# BACKPMAN21_Charger.net
KiCad netlist of a schematic drawn in Altium Designer
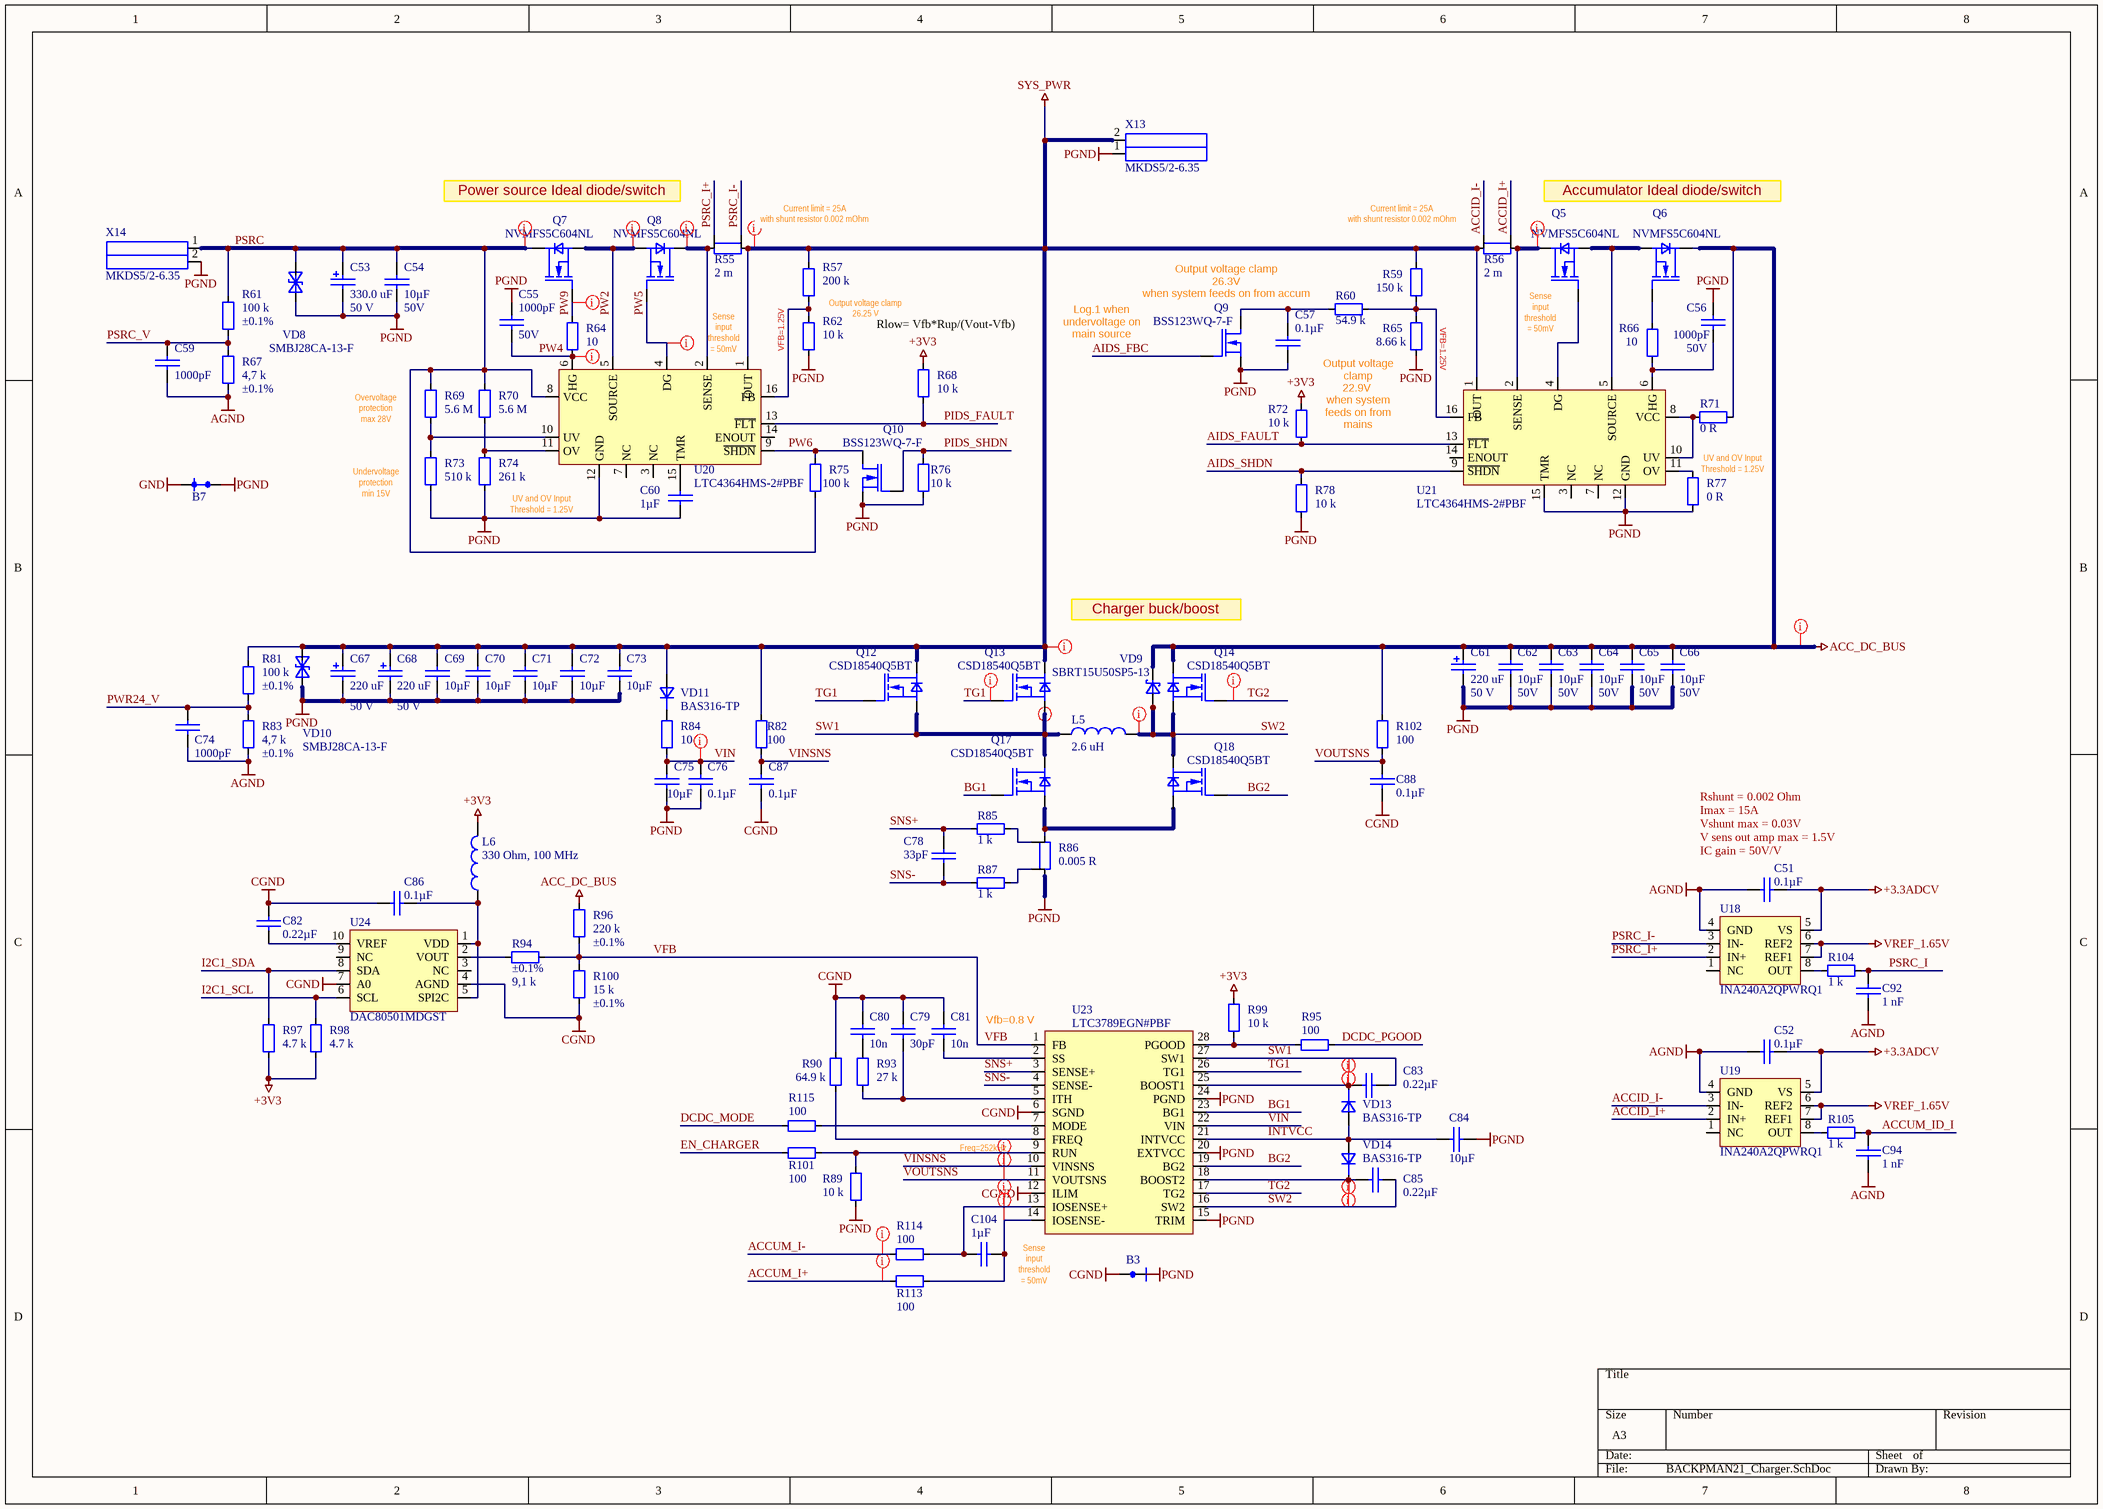
[diagram p0: BACKPMAN21_Charger.SchDoc]

(export (version "E")
  (design (tool "Eeschema 10.0.6"))
  (components
    (comp (ref "B3")
      (value "Net tie 0.3mm")
      (footprint "Net tee 0.3 mm")
      (libsource (lib "ea_Mechanical") (part "Net tie 0.3mm"))
    )
    (comp (ref "B7")
      (value "Net tie 1206")
      (footprint "Net tee 1206")
      (libsource (lib "ea_Mechanical") (part "Net tie 1206"))
    )
    (comp (ref "C51")
      (value "0.1µF")
      (footprint "0603 CAP")
      (description "0.1µF, ±10%, 50V, X8L, 0603 (1608 Metric), -55°C ~ 150°C, -, Automotive")
      (fields
        (field (name "PART NUMBER") "GCM188L81H104KA57D")
        (field (name "MANUFACTURER") "Murata Electronics North America")
      )
      (libsource (lib "ea_PassivComps") (part "Capacitor"))
    )
    (comp (ref "C52")
      (value "0.1µF")
      (footprint "0603 CAP")
      (description "0.1µF, ±10%, 50V, X8L, 0603 (1608 Metric), -55°C ~ 150°C, -, Automotive")
      (fields
        (field (name "PART NUMBER") "GCM188L81H104KA57D")
        (field (name "MANUFACTURER") "Murata Electronics North America")
      )
      (libsource (lib "ea_PassivComps") (part "Capacitor"))
    )
    (comp (ref "C53")
      (value "330.0 uF")
      (footprint "UUD1V331MNL1GS")
      (description "330 uF, 50V, 120 mOhm @ 100kHz, 585 mA, 10x10, -50...+105 C")
      (fields
        (field (name "MANUFACTURER") "Panasonic Electronic Components")
        (field (name "VOLTAGE") "50 V")
        (field (name "TOLERANCE") "±20%")
      )
      (libsource (lib "ea_Capacitors") (part "EEE-FT1H331GP"))
    )
    (comp (ref "C54")
      (value "10µF")
      (footprint "1210 CAP")
      (description "10µF, ±10%, 50V, X7S, 1210 (3225 Metric), -55°C ~ 125°C, Low ESL, General Purpose")
      (fields
        (field (name "VOLTAGE - RATED") "50V")
        (field (name "PART NUMBER") "C3225X7S1H106K250AB")
        (field (name "MANUFACTURER") "TDK Corporation")
      )
      (libsource (lib "ea_PassivComps") (part "Capacitor"))
    )
    (comp (ref "C55")
      (value "1000pF")
      (footprint "0603 CAP")
      (description "1000pF, ±10%, 50V, X7R, 0603 (1608 Metric), -55°C ~ 125°C, -, General Purpose")
      (fields
        (field (name "VOLTAGE - RATED") "50V")
        (field (name "PART NUMBER") "CL10B102KB8NNWC")
        (field (name "MANUFACTURER") "Samsung Electro-Mechanics")
      )
      (libsource (lib "ea_PassivComps") (part "Capacitor"))
    )
    (comp (ref "C56")
      (value "1000pF")
      (footprint "0603 CAP")
      (description "1000pF, ±10%, 50V, X7R, 0603 (1608 Metric), -55°C ~ 125°C, -, General Purpose")
      (fields
        (field (name "VOLTAGE - RATED") "50V")
        (field (name "PART NUMBER") "CL10B102KB8NNWC")
        (field (name "MANUFACTURER") "Samsung Electro-Mechanics")
      )
      (libsource (lib "ea_PassivComps") (part "Capacitor"))
    )
    (comp (ref "C57")
      (value "0.1µF")
      (footprint "0603 CAP")
      (description "0.1µF, ±10%, 16V, X7R, 0603 (1608 Metric), -55°C ~ 125°C, -, General Purpose")
      (fields
        (field (name "PART NUMBER") "CL10B104KO8NNNC")
        (field (name "MANUFACTURER") "Samsung Electro-Mechanics")
      )
      (libsource (lib "ea_PassivComps") (part "Capacitor"))
    )
    (comp (ref "C59")
      (value "1000pF")
      (footprint "0603 CAP")
      (description "1000pF, ±10%, 16V, X7R, 0603 (1608 Metric), -55°C ~ 125°C, -, General Purpose")
      (fields
        (field (name "PART NUMBER") "885012206034")
        (field (name "MANUFACTURER") "Wurth Electronics Inc.")
      )
      (libsource (lib "ea_PassivComps") (part "Capacitor"))
    )
    (comp (ref "C60")
      (value "1µF")
      (footprint "0603 CAP")
      (description "1µF, ±10%, 16V, X7R, 0603 (1608 Metric), -55°C ~ 125°C, -, General Purpose")
      (fields
        (field (name "PART NUMBER") "CL10B105KO8NNNC")
        (field (name "MANUFACTURER") "Samsung Electro-Mechanics")
      )
      (libsource (lib "ea_PassivComps") (part "Capacitor"))
    )
    (comp (ref "C61")
      (value "220 uF")
      (footprint "Panasonic G")
      (description "220 uF, 50V, 13 mOhm, 3.7 A 100kHz, 16.8 mm height, 10.3x10.3 mm, -55...+105 C")
      (fields
        (field (name "MANUFACTURER") "Panasonic Electronic Components")
        (field (name "TOLERANCE") "±20%")
        (field (name "VOLTAGE") "50 V")
      )
      (libsource (lib "ea_Capacitors") (part "EEH-ZS1H221P"))
    )
    (comp (ref "C62")
      (value "10µF")
      (footprint "1210 CAP")
      (description "10µF, ±10%, 50V, X7S, 1210 (3225 Metric), -55°C ~ 125°C, Low ESL, General Purpose")
      (fields
        (field (name "VOLTAGE - RATED") "50V")
        (field (name "PART NUMBER") "C3225X7S1H106K250AB")
        (field (name "MANUFACTURER") "TDK Corporation")
      )
      (libsource (lib "ea_PassivComps") (part "Capacitor"))
    )
    (comp (ref "C63")
      (value "10µF")
      (footprint "1210 CAP")
      (description "10µF, ±10%, 50V, X7S, 1210 (3225 Metric), -55°C ~ 125°C, Low ESL, General Purpose")
      (fields
        (field (name "VOLTAGE - RATED") "50V")
        (field (name "PART NUMBER") "C3225X7S1H106K250AB")
        (field (name "MANUFACTURER") "TDK Corporation")
      )
      (libsource (lib "ea_PassivComps") (part "Capacitor"))
    )
    (comp (ref "C64")
      (value "10µF")
      (footprint "1210 CAP")
      (description "10µF, ±10%, 50V, X7S, 1210 (3225 Metric), -55°C ~ 125°C, Low ESL, General Purpose")
      (fields
        (field (name "VOLTAGE - RATED") "50V")
        (field (name "PART NUMBER") "C3225X7S1H106K250AB")
        (field (name "MANUFACTURER") "TDK Corporation")
      )
      (libsource (lib "ea_PassivComps") (part "Capacitor"))
    )
    (comp (ref "C65")
      (value "10µF")
      (footprint "1210 CAP")
      (description "10µF, ±10%, 50V, X7S, 1210 (3225 Metric), -55°C ~ 125°C, Low ESL, General Purpose")
      (fields
        (field (name "VOLTAGE - RATED") "50V")
        (field (name "PART NUMBER") "C3225X7S1H106K250AB")
        (field (name "MANUFACTURER") "TDK Corporation")
      )
      (libsource (lib "ea_PassivComps") (part "Capacitor"))
    )
    (comp (ref "C66")
      (value "10µF")
      (footprint "1210 CAP")
      (description "10µF, ±10%, 50V, X7S, 1210 (3225 Metric), -55°C ~ 125°C, Low ESL, General Purpose")
      (fields
        (field (name "VOLTAGE - RATED") "50V")
        (field (name "PART NUMBER") "C3225X7S1H106K250AB")
        (field (name "MANUFACTURER") "TDK Corporation")
      )
      (libsource (lib "ea_PassivComps") (part "Capacitor"))
    )
    (comp (ref "C67")
      (value "220 uF")
      (footprint "Panasonic G")
      (description "220 uF, 50V, 13 mOhm, 3.7 A 100kHz, 16.8 mm height, 10.3x10.3 mm, -55...+105 C")
      (fields
        (field (name "MANUFACTURER") "Panasonic Electronic Components")
        (field (name "TOLERANCE") "±20%")
        (field (name "VOLTAGE") "50 V")
      )
      (libsource (lib "ea_Capacitors") (part "EEH-ZS1H221P"))
    )
    (comp (ref "C68")
      (value "220 uF")
      (footprint "Panasonic G")
      (description "220 uF, 50V, 13 mOhm, 3.7 A 100kHz, 16.8 mm height, 10.3x10.3 mm, -55...+105 C")
      (fields
        (field (name "MANUFACTURER") "Panasonic Electronic Components")
        (field (name "TOLERANCE") "±20%")
        (field (name "VOLTAGE") "50 V")
      )
      (libsource (lib "ea_Capacitors") (part "EEH-ZS1H221P"))
    )
    (comp (ref "C69")
      (value "10µF")
      (footprint "1210 CAP")
      (description "10µF, ±10%, 50V, X7S, 1210 (3225 Metric), -55°C ~ 125°C, Low ESL, General Purpose")
      (fields
        (field (name "PART NUMBER") "C3225X7S1H106K250AB")
        (field (name "MANUFACTURER") "TDK Corporation")
      )
      (libsource (lib "ea_PassivComps") (part "Capacitor"))
    )
    (comp (ref "C70")
      (value "10µF")
      (footprint "1210 CAP")
      (description "10µF, ±10%, 50V, X7S, 1210 (3225 Metric), -55°C ~ 125°C, Low ESL, General Purpose")
      (fields
        (field (name "PART NUMBER") "C3225X7S1H106K250AB")
        (field (name "MANUFACTURER") "TDK Corporation")
      )
      (libsource (lib "ea_PassivComps") (part "Capacitor"))
    )
    (comp (ref "C71")
      (value "10µF")
      (footprint "1210 CAP")
      (description "10µF, ±10%, 50V, X7S, 1210 (3225 Metric), -55°C ~ 125°C, Low ESL, General Purpose")
      (fields
        (field (name "PART NUMBER") "C3225X7S1H106K250AB")
        (field (name "MANUFACTURER") "TDK Corporation")
      )
      (libsource (lib "ea_PassivComps") (part "Capacitor"))
    )
    (comp (ref "C72")
      (value "10µF")
      (footprint "1210 CAP")
      (description "10µF, ±10%, 50V, X7S, 1210 (3225 Metric), -55°C ~ 125°C, Low ESL, General Purpose")
      (fields
        (field (name "PART NUMBER") "C3225X7S1H106K250AB")
        (field (name "MANUFACTURER") "TDK Corporation")
      )
      (libsource (lib "ea_PassivComps") (part "Capacitor"))
    )
    (comp (ref "C73")
      (value "10µF")
      (footprint "1210 CAP")
      (description "10µF, ±10%, 50V, X7S, 1210 (3225 Metric), -55°C ~ 125°C, Low ESL, General Purpose")
      (fields
        (field (name "PART NUMBER") "C3225X7S1H106K250AB")
        (field (name "MANUFACTURER") "TDK Corporation")
      )
      (libsource (lib "ea_PassivComps") (part "Capacitor"))
    )
    (comp (ref "C74")
      (value "1000pF")
      (footprint "0603 CAP")
      (description "1000pF, ±10%, 16V, X7R, 0603 (1608 Metric), -55°C ~ 125°C, -, General Purpose")
      (fields
        (field (name "PART NUMBER") "885012206034")
        (field (name "MANUFACTURER") "Wurth Electronics Inc.")
      )
      (libsource (lib "ea_PassivComps") (part "Capacitor"))
    )
    (comp (ref "C75")
      (value "10µF")
      (footprint "1210 CAP")
      (description "10µF, ±10%, 50V, X7S, 1210 (3225 Metric), -55°C ~ 125°C, Low ESL, General Purpose")
      (fields
        (field (name "PART NUMBER") "C3225X7S1H106K250AB")
        (field (name "MANUFACTURER") "TDK Corporation")
      )
      (libsource (lib "ea_PassivComps") (part "Capacitor"))
    )
    (comp (ref "C76")
      (value "0.1µF")
      (footprint "0603 CAP")
      (description "0.1µF, ±10%, 50V, X8L, 0603 (1608 Metric), -55°C ~ 150°C, -, Automotive")
      (fields
        (field (name "PART NUMBER") "GCM188L81H104KA57D")
        (field (name "MANUFACTURER") "Murata Electronics North America")
      )
      (libsource (lib "ea_PassivComps") (part "Capacitor"))
    )
    (comp (ref "C78")
      (value "33pF")
      (footprint "0603 CAP")
      (description "33pF, ±5%, 50V, C0G, NP0, 0603 (1608 Metric), -55°C ~ 125°C, -, General Purpose")
      (fields
        (field (name "PART NUMBER") "885012006054")
        (field (name "MANUFACTURER") "Wurth Electronics Inc.")
      )
      (libsource (lib "ea_PassivComps") (part "Capacitor"))
    )
    (comp (ref "C79")
      (value "30pF")
      (footprint "0603 CAP")
      (description "30pF, ±5%, 50V, C0G, NP0, 0603 (1608 Metric), -55°C ~ 125°C, -, General Purpose")
      (fields
        (field (name "PART NUMBER") "CL10C300JB8NCNC")
        (field (name "MANUFACTURER") "Samsung Electro-Mechanics")
      )
      (libsource (lib "ea_PassivComps") (part "Capacitor"))
    )
    (comp (ref "C80")
      (value "10n")
      (footprint "0603 CAP")
      (description "10000pF, ±10%, 25V, X7R, 0603 (1608 Metric), -55°C ~ 125°C, -, General Purpose")
      (fields (field (name "PART NUMBER") "C0603C103K3RACTU") (field (name "MANUFACTURER") "KEMET"))
      (libsource (lib "ea_PassivComps") (part "Capacitor"))
    )
    (comp (ref "C81")
      (value "10n")
      (footprint "0603 CAP")
      (description "10000pF, ±10%, 25V, X7R, 0603 (1608 Metric), -55°C ~ 125°C, -, General Purpose")
      (fields (field (name "PART NUMBER") "C0603C103K3RACTU") (field (name "MANUFACTURER") "KEMET"))
      (libsource (lib "ea_PassivComps") (part "Capacitor"))
    )
    (comp (ref "C82")
      (value "0.22µF")
      (footprint "0603 CAP")
      (description "0.22µF, ±10%, 16V, X7R, 0603 (1608 Metric), -55°C ~ 125°C, -, General Purpose")
      (fields
        (field (name "PART NUMBER") "GRM188R71C224KA01J")
        (field (name "MANUFACTURER") "Murata Electronics North America")
      )
      (libsource (lib "ea_PassivComps") (part "Capacitor"))
    )
    (comp (ref "C83")
      (value "0.22µF")
      (footprint "0603 CAP")
      (description "0.22µF, ±10%, 16V, X7R, 0603 (1608 Metric), -55°C ~ 125°C, -, General Purpose")
      (fields
        (field (name "PART NUMBER") "GRM188R71C224KA01J")
        (field (name "MANUFACTURER") "Murata Electronics North America")
      )
      (libsource (lib "ea_PassivComps") (part "Capacitor"))
    )
    (comp (ref "C84")
      (value "10µF")
      (footprint "0603 CAP")
      (description "10µF, ±20%, 25V, X5R, 0603 (1608 Metric), -55°C ~ 85°C, Low ESL, General Purpose")
      (fields
        (field (name "PART NUMBER") "C1608X5R1E106M080AC")
        (field (name "MANUFACTURER") "TDK Corporation")
      )
      (libsource (lib "ea_PassivComps") (part "Capacitor"))
    )
    (comp (ref "C85")
      (value "0.22µF")
      (footprint "0603 CAP")
      (description "0.22µF, ±10%, 16V, X7R, 0603 (1608 Metric), -55°C ~ 125°C, -, General Purpose")
      (fields
        (field (name "PART NUMBER") "GRM188R71C224KA01J")
        (field (name "MANUFACTURER") "Murata Electronics North America")
      )
      (libsource (lib "ea_PassivComps") (part "Capacitor"))
    )
    (comp (ref "C86")
      (value "0.1µF")
      (footprint "0603 CAP")
      (description "0.1µF, ±10%, 16V, X7R, 0603 (1608 Metric), -55°C ~ 125°C, -, General Purpose")
      (fields
        (field (name "PART NUMBER") "CL10B104KO8NNNC")
        (field (name "MANUFACTURER") "Samsung Electro-Mechanics")
      )
      (libsource (lib "ea_PassivComps") (part "Capacitor"))
    )
    (comp (ref "C87")
      (value "0.1µF")
      (footprint "0603 CAP")
      (description "0.1µF, ±10%, 50V, X8L, 0603 (1608 Metric), -55°C ~ 150°C, -, Automotive")
      (fields
        (field (name "PART NUMBER") "GCM188L81H104KA57D")
        (field (name "MANUFACTURER") "Murata Electronics North America")
      )
      (libsource (lib "ea_PassivComps") (part "Capacitor"))
    )
    (comp (ref "C88")
      (value "0.1µF")
      (footprint "0603 CAP")
      (description "0.1µF, ±10%, 50V, X8L, 0603 (1608 Metric), -55°C ~ 150°C, -, Automotive")
      (fields
        (field (name "PART NUMBER") "GCM188L81H104KA57D")
        (field (name "MANUFACTURER") "Murata Electronics North America")
      )
      (libsource (lib "ea_PassivComps") (part "Capacitor"))
    )
    (comp (ref "C92")
      (value "1 nF")
      (footprint "0603 CAP")
      (description "1000pF, ±5%, 50V, X7R, 0603 (1608 Metric), -55°C ~ 125°C, -, General Purpose")
      (fields (field (name "PART NUMBER") "CC0603JRX7R9BB102") (field (name "MANUFACTURER") "Yageo"))
      (libsource (lib "ea_PassivComps") (part "Capacitor"))
    )
    (comp (ref "C94")
      (value "1 nF")
      (footprint "0603 CAP")
      (description "1000pF, ±5%, 50V, X7R, 0603 (1608 Metric), -55°C ~ 125°C, -, General Purpose")
      (fields (field (name "PART NUMBER") "CC0603JRX7R9BB102") (field (name "MANUFACTURER") "Yageo"))
      (libsource (lib "ea_PassivComps") (part "Capacitor"))
    )
    (comp (ref "C104")
      (value "1µF")
      (footprint "0603 CAP")
      (description "1µF, ±10%, 16V, X7R, 0603 (1608 Metric), -55°C ~ 125°C, -, General Purpose")
      (fields
        (field (name "PART NUMBER") "CL10B105KO8NNNC")
        (field (name "MANUFACTURER") "Samsung Electro-Mechanics")
      )
      (libsource (lib "ea_PassivComps") (part "Capacitor"))
    )
    (comp (ref "L5")
      (value "2.6 uH")
      (footprint "7443556260   Wurth Elektronik")
      (description "2.6 uH, 31.5 A, ±20%, 1.58 mOhm, -40°C ~ 125°C")
      (fields (field (name "MANUFACTURER") "Würth Elektronik") (field (name "PARTNUM") "732-2170-1-ND"))
      (libsource (lib "ea_Inductors") (part "7443556260"))
    )
    (comp (ref "L6")
      (value "330 Ohm, 100 MHz")
      (footprint "0603")
      (description "Ferrite bead, 330 Ohm, 100 MHz,  1.5 A, 0.07 Ohm")
      (fields
        (field (name "MANUFACTURER") "Murata Electronics North America")
        (field (name "PARTNUM") "BLM18SG331TN1D")
      )
      (libsource (lib "*") (part "BLM18SG331TN1D"))
    )
    (comp (ref "Q5")
      (value "NVMFS5C604NL")
      (footprint "SO8FL Universal Footprint")
      (description "MOSFET N-CH, 287 A, 60V, Vgs=±20V, 1.2 mOhm, 52nC @ 4.5V, 5-DFN (5x6), -55°C ~ 175°C")
      (fields
        (field (name "MANUFACTURER") "Texas Instruments")
        (field (name "PARTNUM") "NVMFS5C604NLAFT1GOSCT-ND")
      )
      (libsource (lib "ea_MOSFET_&_drivers") (part "NVMFS5C604NLAFT1G"))
    )
    (comp (ref "Q6")
      (value "NVMFS5C604NL")
      (footprint "SO8FL Universal Footprint")
      (description "MOSFET N-CH, 287 A, 60V, Vgs=±20V, 1.2 mOhm, 52nC @ 4.5V, 5-DFN (5x6), -55°C ~ 175°C")
      (fields
        (field (name "MANUFACTURER") "Texas Instruments")
        (field (name "PARTNUM") "NVMFS5C604NLAFT1GOSCT-ND")
      )
      (libsource (lib "ea_MOSFET_&_drivers") (part "NVMFS5C604NLAFT1G"))
    )
    (comp (ref "Q7")
      (value "NVMFS5C604NL")
      (footprint "SO8FL Universal Footprint")
      (description "MOSFET N-CH, 287 A, 60V, Vgs=±20V, 1.2 mOhm, 52nC @ 4.5V, 5-DFN (5x6), -55°C ~ 175°C")
      (fields
        (field (name "MANUFACTURER") "Texas Instruments")
        (field (name "PARTNUM") "NVMFS5C604NLAFT1GOSCT-ND")
      )
      (libsource (lib "ea_MOSFET_&_drivers") (part "NVMFS5C604NLAFT1G"))
    )
    (comp (ref "Q8")
      (value "NVMFS5C604NL")
      (footprint "SO8FL Universal Footprint")
      (description "MOSFET N-CH, 287 A, 60V, Vgs=±20V, 1.2 mOhm, 52nC @ 4.5V, 5-DFN (5x6), -55°C ~ 175°C")
      (fields
        (field (name "MANUFACTURER") "Texas Instruments")
        (field (name "PARTNUM") "NVMFS5C604NLAFT1GOSCT-ND")
      )
      (libsource (lib "ea_MOSFET_&_drivers") (part "NVMFS5C604NLAFT1G"))
    )
    (comp (ref "Q9")
      (value "BSS123WQ-7-F")
      (footprint "SOT323-3")
      (description "MOSFETs N-CH, 2V @ 1mA, 6 Ohm @ 170mA, 10V, 170mA, 100V, SOT-323,  -55°C ~ 150°C")
      (fields
        (field (name "MANUFACTURER") "Diodes Incorporated")
        (field (name "PARTNUM") "BSS123WQ-7-FDICT-ND")
      )
      (libsource (lib "") (part "BSS123WQ-7-F_1"))
    )
    (comp (ref "Q10")
      (value "BSS123WQ-7-F")
      (footprint "SOT323-3")
      (description "MOSFETs N-CH, 2V @ 1mA, 6 Ohm @ 170mA, 10V, 170mA, 100V, SOT-323,  -55°C ~ 150°C")
      (fields
        (field (name "MANUFACTURER") "Diodes Incorporated")
        (field (name "PARTNUM") "BSS123WQ-7-FDICT-ND")
      )
      (libsource (lib "ea_Transistors") (part "BSS123WQ-7-F"))
    )
    (comp (ref "Q12")
      (value "CSD18540Q5BT")
      (footprint "SO8FL Universal Footprint")
      (description "MOSFET N-CH, 100 A, 60V, Vgs=±20V, 1.8 mOhm, 41nC @ 10V, 5-DFN (5x6), -55°C ~ 150°C")
      (fields (field (name "MANUFACTURER") "Texas Instruments") (field (name "PARTNUM") "296-37963-1-ND"))
      (libsource (lib "") (part "CSD18540Q5BT_1"))
    )
    (comp (ref "Q13")
      (value "CSD18540Q5BT")
      (footprint "SO8FL Universal Footprint")
      (description "MOSFET N-CH, 100 A, 60V, Vgs=±20V, 1.8 mOhm, 41nC @ 10V, 5-DFN (5x6), -55°C ~ 150°C")
      (fields (field (name "MANUFACTURER") "Texas Instruments") (field (name "PARTNUM") "296-37963-1-ND"))
      (libsource (lib "") (part "CSD18540Q5BT_1"))
    )
    (comp (ref "Q14")
      (value "CSD18540Q5BT")
      (footprint "SO8FL Universal Footprint")
      (description "MOSFET N-CH, 100 A, 60V, Vgs=±20V, 1.8 mOhm, 41nC @ 10V, 5-DFN (5x6), -55°C ~ 150°C")
      (fields (field (name "MANUFACTURER") "Texas Instruments") (field (name "PARTNUM") "296-37963-1-ND"))
      (libsource (lib "ea_MOSFET_&_drivers") (part "CSD18540Q5BT"))
    )
    (comp (ref "Q17")
      (value "CSD18540Q5BT")
      (footprint "SO8FL Universal Footprint")
      (description "MOSFET N-CH, 100 A, 60V, Vgs=±20V, 1.8 mOhm, 41nC @ 10V, 5-DFN (5x6), -55°C ~ 150°C")
      (fields (field (name "MANUFACTURER") "Texas Instruments") (field (name "PARTNUM") "296-37963-1-ND"))
      (libsource (lib "") (part "CSD18540Q5BT_1"))
    )
    (comp (ref "Q18")
      (value "CSD18540Q5BT")
      (footprint "SO8FL Universal Footprint")
      (description "MOSFET N-CH, 100 A, 60V, Vgs=±20V, 1.8 mOhm, 41nC @ 10V, 5-DFN (5x6), -55°C ~ 150°C")
      (fields (field (name "MANUFACTURER") "Texas Instruments") (field (name "PARTNUM") "296-37963-1-ND"))
      (libsource (lib "ea_MOSFET_&_drivers") (part "CSD18540Q5BT"))
    )
    (comp (ref "R55")
      (value "2 m")
      (footprint "2512 shunt")
      (fields
        (field (name "MANUFACTURER") "Vishay Dale")
        (field (name "TOLERANCE") "±1%")
        (field (name "PARTNUM") "541-3126-1-ND")
      )
      (libsource (lib "ea_PassivComps") (part "Resistor_shunt"))
    )
    (comp (ref "R56")
      (value "2 m")
      (footprint "2512 shunt")
      (fields
        (field (name "MANUFACTURER") "Vishay Dale")
        (field (name "TOLERANCE") "±1%")
        (field (name "PARTNUM") "541-3126-1-ND")
      )
      (libsource (lib "ea_PassivComps") (part "Resistor_shunt"))
    )
    (comp (ref "R57")
      (value "200 k")
      (footprint "1206")
      (fields
        (field (name "MANUFACTURER") "Stackpole Electronics Inc.")
        (field (name "TOLERANCE") "±1%")
        (field (name "VOLTAGE") "200V")
      )
      (libsource (lib "ea_PassivComps") (part "Resistor"))
    )
    (comp (ref "R59")
      (value "150 k")
      (footprint "1206")
      (fields
        (field (name "MANUFACTURER") "Stackpole Electronics Inc.")
        (field (name "TOLERANCE") "±1%")
        (field (name "VOLTAGE") "200V")
      )
      (libsource (lib "") (part "Resistor_3"))
    )
    (comp (ref "R60")
      (value "54.9 k")
      (footprint "0603")
      (fields
        (field (name "MANUFACTURER") "Stackpole Electronics Inc.")
        (field (name "TOLERANCE") "±1%")
        (field (name "VOLTAGE") "75V")
      )
      (libsource (lib "") (part "Resistor_1"))
    )
    (comp (ref "R61")
      (value "100 k")
      (footprint "1206")
      (fields
        (field (name "MANUFACTURER") "Panasonic Electronic Components")
        (field (name "TOLERANCE") "±0.1%")
        (field (name "VOLTAGE") "200V")
        (field (name "PARTNUM") "ERA-8APB104V")
      )
      (libsource (lib "") (part "Resistor_3"))
    )
    (comp (ref "R62")
      (value "10 k")
      (footprint "0603")
      (fields
        (field (name "MANUFACTURER") "Bourns Inc.")
        (field (name "TOLERANCE") "±1%")
        (field (name "VOLTAGE") "75V")
      )
      (libsource (lib "") (part "Resistor_1"))
    )
    (comp (ref "R64")
      (value "10")
      (footprint "0805")
      (fields
        (field (name "MANUFACTURER") "Stackpole Electronics Inc.")
        (field (name "TOLERANCE") "±1%")
        (field (name "VOLTAGE") "150V")
      )
      (libsource (lib "ea_PassivComps") (part "Resistor"))
    )
    (comp (ref "R65")
      (value "8.66 k")
      (footprint "0603")
      (fields
        (field (name "MANUFACTURER") "Stackpole Electronics Inc.")
        (field (name "TOLERANCE") "±1%")
        (field (name "VOLTAGE") "75V")
      )
      (libsource (lib "") (part "Resistor_3"))
    )
    (comp (ref "R66")
      (value "10")
      (footprint "0805")
      (fields
        (field (name "MANUFACTURER") "Stackpole Electronics Inc.")
        (field (name "TOLERANCE") "±1%")
        (field (name "VOLTAGE") "150V")
      )
      (libsource (lib "") (part "Resistor_3"))
    )
    (comp (ref "R67")
      (value "4,7 k")
      (footprint "0603")
      (fields
        (field (name "MANUFACTURER") "Panasonic Electronic Components")
        (field (name "TOLERANCE") "±0.1%")
        (field (name "VOLTAGE") "75V")
        (field (name "PARTNUM") "P4.7KDBCT-ND")
      )
      (libsource (lib "ea_PassivComps") (part "Resistor"))
    )
    (comp (ref "R68")
      (value "10 k")
      (footprint "0603")
      (fields
        (field (name "MANUFACTURER") "Bourns Inc.")
        (field (name "TOLERANCE") "±1%")
        (field (name "VOLTAGE") "75V")
      )
      (libsource (lib "ea_PassivComps") (part "Resistor"))
    )
    (comp (ref "R69")
      (value "5.6 M")
      (footprint "1206")
      (fields
        (field (name "MANUFACTURER") "Yageo")
        (field (name "TOLERANCE") "±1%")
        (field (name "VOLTAGE") "200V")
      )
      (libsource (lib "ea_PassivComps") (part "Resistor"))
    )
    (comp (ref "R70")
      (value "5.6 M")
      (footprint "1206")
      (fields
        (field (name "MANUFACTURER") "Yageo")
        (field (name "TOLERANCE") "±1%")
        (field (name "VOLTAGE") "200V")
      )
      (libsource (lib "ea_PassivComps") (part "Resistor"))
    )
    (comp (ref "R71")
      (value "0 R")
      (footprint "0603")
      (description "0 R, Jumper, 0603, SMD Resistor, -55°C ~ 155°C")
      (fields (field (name "MANUFACTURER") "Yageo") (field (name "VOLTAGE") "75 V"))
      (libsource (lib "") (part "RC0603FR-070RL_1"))
    )
    (comp (ref "R72")
      (value "10 k")
      (footprint "0603")
      (fields
        (field (name "MANUFACTURER") "Bourns Inc.")
        (field (name "TOLERANCE") "±1%")
        (field (name "VOLTAGE") "75V")
      )
      (libsource (lib "ea_PassivComps") (part "Resistor"))
    )
    (comp (ref "R73")
      (value "510 k")
      (footprint "0603")
      (fields
        (field (name "MANUFACTURER") "Stackpole Electronics Inc.")
        (field (name "TOLERANCE") "±1%")
        (field (name "VOLTAGE") "75V")
      )
      (libsource (lib "ea_PassivComps") (part "Resistor"))
    )
    (comp (ref "R74")
      (value "261 k")
      (footprint "0603")
      (fields
        (field (name "MANUFACTURER") "Vishay Dale")
        (field (name "TOLERANCE") "±1%")
        (field (name "VOLTAGE") "75V")
      )
      (libsource (lib "ea_PassivComps") (part "Resistor"))
    )
    (comp (ref "R75")
      (value "100 k")
      (footprint "1206")
      (fields
        (field (name "MANUFACTURER") "Stackpole Electronics Inc.")
        (field (name "TOLERANCE") "±1%")
        (field (name "VOLTAGE") "200V")
      )
      (libsource (lib "ea_PassivComps") (part "Resistor"))
    )
    (comp (ref "R76")
      (value "10 k")
      (footprint "0603")
      (fields
        (field (name "MANUFACTURER") "Bourns Inc.")
        (field (name "TOLERANCE") "±1%")
        (field (name "VOLTAGE") "75V")
      )
      (libsource (lib "ea_PassivComps") (part "Resistor"))
    )
    (comp (ref "R77")
      (value "0 R")
      (footprint "0603")
      (description "0 R, Jumper, 0603, SMD Resistor, -55°C ~ 155°C")
      (fields (field (name "MANUFACTURER") "Yageo") (field (name "VOLTAGE") "75 V"))
      (libsource (lib "ea_Resistors_0603") (part "RC0603FR-070RL"))
    )
    (comp (ref "R78")
      (value "10 k")
      (footprint "0603")
      (fields
        (field (name "MANUFACTURER") "Bourns Inc.")
        (field (name "TOLERANCE") "±1%")
        (field (name "VOLTAGE") "75V")
      )
      (libsource (lib "") (part "Resistor_3"))
    )
    (comp (ref "R81")
      (value "100 k")
      (footprint "1206")
      (fields
        (field (name "MANUFACTURER") "Panasonic Electronic Components")
        (field (name "TOLERANCE") "±0.1%")
        (field (name "VOLTAGE") "200V")
        (field (name "PARTNUM") "ERA-8APB104V")
      )
      (libsource (lib "") (part "Resistor_3"))
    )
    (comp (ref "R82")
      (value "100")
      (footprint "0603")
      (fields
        (field (name "MANUFACTURER") "Stackpole Electronics Inc.")
        (field (name "TOLERANCE") "±1%")
        (field (name "VOLTAGE") "75V")
      )
      (libsource (lib "ea_PassivComps") (part "Resistor"))
    )
    (comp (ref "R83")
      (value "4,7 k")
      (footprint "0603")
      (fields
        (field (name "MANUFACTURER") "Panasonic Electronic Components")
        (field (name "TOLERANCE") "±0.1%")
        (field (name "VOLTAGE") "75V")
        (field (name "PARTNUM") "P4.7KDBCT-ND")
      )
      (libsource (lib "ea_PassivComps") (part "Resistor"))
    )
    (comp (ref "R84")
      (value "10")
      (footprint "0805")
      (fields
        (field (name "MANUFACTURER") "Stackpole Electronics Inc.")
        (field (name "TOLERANCE") "±1%")
        (field (name "VOLTAGE") "150V")
      )
      (libsource (lib "ea_PassivComps") (part "Resistor"))
    )
    (comp (ref "R85")
      (value "1 k")
      (footprint "0603")
      (fields
        (field (name "MANUFACTURER") "Stackpole Electronics Inc.")
        (field (name "TOLERANCE") "±1%")
        (field (name "VOLTAGE") "75V")
      )
      (libsource (lib "") (part "Resistor_2"))
    )
    (comp (ref "R86")
      (value "0.005 R")
      (footprint "FC4L110")
      (description "Curr.sens.res. 0.005 OHM 5W 1% , 4320 (50110 Metric)")
      (fields (field (name "MANUFACTURER") "Ohmite") (field (name "TOLERANCE") "1%"))
      (libsource (lib "ea_Resistors") (part "FC4L110R005FER"))
    )
    (comp (ref "R87")
      (value "1 k")
      (footprint "0603")
      (fields
        (field (name "MANUFACTURER") "Stackpole Electronics Inc.")
        (field (name "TOLERANCE") "±1%")
        (field (name "VOLTAGE") "75V")
      )
      (libsource (lib "") (part "Resistor_2"))
    )
    (comp (ref "R89")
      (value "10 k")
      (footprint "0603")
      (fields
        (field (name "MANUFACTURER") "Bourns Inc.")
        (field (name "TOLERANCE") "±1%")
        (field (name "VOLTAGE") "75V")
      )
      (libsource (lib "ea_PassivComps") (part "Resistor"))
    )
    (comp (ref "R90")
      (value "64.9 k")
      (footprint "0603")
      (fields
        (field (name "MANUFACTURER") "Stackpole Electronics Inc.")
        (field (name "TOLERANCE") "±1%")
        (field (name "VOLTAGE") "75V")
      )
      (libsource (lib "") (part "Resistor_1"))
    )
    (comp (ref "R93")
      (value "27 k")
      (footprint "0603")
      (fields
        (field (name "MANUFACTURER") "Stackpole Electronics Inc.")
        (field (name "TOLERANCE") "±1%")
        (field (name "VOLTAGE") "75V")
      )
      (libsource (lib "ea_PassivComps") (part "Resistor"))
    )
    (comp (ref "R94")
      (value "9,1 k")
      (footprint "0603")
      (fields
        (field (name "MANUFACTURER") "Panasonic Electronic Components")
        (field (name "TOLERANCE") "±0.1%")
        (field (name "VOLTAGE") "75V")
        (field (name "PARTNUM") "P9.1KDBCT-ND")
      )
      (libsource (lib "") (part "Resistor_2"))
    )
    (comp (ref "R95")
      (value "100")
      (footprint "0603")
      (fields
        (field (name "MANUFACTURER") "Stackpole Electronics Inc.")
        (field (name "TOLERANCE") "±1%")
        (field (name "VOLTAGE") "75V")
      )
      (libsource (lib "") (part "Resistor_1"))
    )
    (comp (ref "R96")
      (value "220 k")
      (footprint "0603")
      (fields
        (field (name "MANUFACTURER") "Panasonic Electronic Components")
        (field (name "TOLERANCE") "±0.1%")
        (field (name "VOLTAGE") "75V")
        (field (name "PARTNUM") "P220KDBCT-ND")
      )
      (libsource (lib "ea_PassivComps") (part "Resistor"))
    )
    (comp (ref "R97")
      (value "4.7 k")
      (footprint "0603")
      (fields
        (field (name "MANUFACTURER") "Stackpole Electronics Inc.")
        (field (name "TOLERANCE") "±1%")
        (field (name "VOLTAGE") "75V")
      )
      (libsource (lib "ea_PassivComps") (part "Resistor"))
    )
    (comp (ref "R98")
      (value "4.7 k")
      (footprint "0603")
      (fields
        (field (name "MANUFACTURER") "Stackpole Electronics Inc.")
        (field (name "TOLERANCE") "±1%")
        (field (name "VOLTAGE") "75V")
      )
      (libsource (lib "ea_PassivComps") (part "Resistor"))
    )
    (comp (ref "R99")
      (value "10 k")
      (footprint "0603")
      (fields
        (field (name "MANUFACTURER") "Bourns Inc.")
        (field (name "TOLERANCE") "±1%")
        (field (name "VOLTAGE") "75V")
      )
      (libsource (lib "") (part "Resistor_2"))
    )
    (comp (ref "R100")
      (value "15 k")
      (footprint "0603")
      (fields
        (field (name "MANUFACTURER") "Panasonic Electronic Components")
        (field (name "TOLERANCE") "±0.1%")
        (field (name "VOLTAGE") "75V")
        (field (name "PARTNUM") "P15KDBCT-ND")
      )
      (libsource (lib "ea_PassivComps") (part "Resistor"))
    )
    (comp (ref "R101")
      (value "100")
      (footprint "0603")
      (fields
        (field (name "MANUFACTURER") "Stackpole Electronics Inc.")
        (field (name "TOLERANCE") "±1%")
        (field (name "VOLTAGE") "75V")
      )
      (libsource (lib "") (part "Resistor_1"))
    )
    (comp (ref "R102")
      (value "100")
      (footprint "0603")
      (fields
        (field (name "MANUFACTURER") "Stackpole Electronics Inc.")
        (field (name "TOLERANCE") "±1%")
        (field (name "VOLTAGE") "75V")
      )
      (libsource (lib "ea_PassivComps") (part "Resistor"))
    )
    (comp (ref "R104")
      (value "1 k")
      (footprint "0603")
      (fields
        (field (name "MANUFACTURER") "Stackpole Electronics Inc.")
        (field (name "TOLERANCE") "±1%")
        (field (name "VOLTAGE") "75V")
      )
      (libsource (lib "") (part "Resistor_3"))
    )
    (comp (ref "R105")
      (value "1 k")
      (footprint "0603")
      (fields
        (field (name "MANUFACTURER") "Stackpole Electronics Inc.")
        (field (name "TOLERANCE") "±1%")
        (field (name "VOLTAGE") "75V")
      )
      (libsource (lib "") (part "Resistor_3"))
    )
    (comp (ref "R113")
      (value "100")
      (footprint "0603")
      (fields
        (field (name "MANUFACTURER") "Stackpole Electronics Inc.")
        (field (name "TOLERANCE") "±1%")
        (field (name "VOLTAGE") "75V")
      )
      (libsource (lib "") (part "Resistor_1"))
    )
    (comp (ref "R114")
      (value "100")
      (footprint "0603")
      (fields
        (field (name "MANUFACTURER") "Stackpole Electronics Inc.")
        (field (name "TOLERANCE") "±1%")
        (field (name "VOLTAGE") "75V")
      )
      (libsource (lib "") (part "Resistor_1"))
    )
    (comp (ref "R115")
      (value "100")
      (footprint "0603")
      (fields
        (field (name "MANUFACTURER") "Stackpole Electronics Inc.")
        (field (name "TOLERANCE") "±1%")
        (field (name "VOLTAGE") "75V")
      )
      (libsource (lib "") (part "Resistor_1"))
    )
    (comp (ref "U18")
      (value "INA240A2QPWRQ1")
      (footprint "TI TSSOP-8")
      (description "Current Sense Amplifier, 50V/V, 2V/us, 400KHz, -40°C ~ 125°C, 8-TSSOP")
      (fields (field (name "MANUFACTURER") "Texas Instruments") (field (name "PARTNUM") "296-50473-1-ND"))
      (libsource (lib "ea_IC_OPAmps_AnComparators") (part "INA240A2QPWRQ1"))
    )
    (comp (ref "U19")
      (value "INA240A2QPWRQ1")
      (footprint "TI TSSOP-8")
      (description "Current Sense Amplifier, 50V/V, 2V/us, 400KHz, -40°C ~ 125°C, 8-TSSOP")
      (fields (field (name "MANUFACTURER") "Texas Instruments") (field (name "PARTNUM") "296-50473-1-ND"))
      (libsource (lib "ea_IC_OPAmps_AnComparators") (part "INA240A2QPWRQ1"))
    )
    (comp (ref "U20")
      (value "LTC4364HMS-2#PBF")
      (footprint "16-Lead Plastic MSOP LINEAR")
      (description "Surge Stopper  with Ideal Diode, 4-80V, 16-Lead MSOP, -40°C...125°C")
      (fields
        (field (name "MANUFACTURER") "Analog Devices")
        (field (name "PARTNUM") "LTC4364HMS-2#PBF-ND")
        (field (name "PARTNAME") "LTC4364HMS-2#PBF")
      )
      (libsource (lib "ea_IC_drivers") (part "LTC4364HMS-2#PBF"))
    )
    (comp (ref "U21")
      (value "LTC4364HMS-2#PBF")
      (footprint "16-Lead Plastic MSOP LINEAR")
      (description "Surge Stopper  with Ideal Diode, 4-80V, 16-Lead MSOP, -40°C...125°C")
      (fields
        (field (name "MANUFACTURER") "Analog Devices")
        (field (name "PARTNUM") "LTC4364HMS-2#PBF-ND")
        (field (name "PARTNAME") "LTC4364HMS-2#PBF")
      )
      (libsource (lib "") (part "LTC4364HMS-2#PBF_1"))
    )
    (comp (ref "U23")
      (value "LTC3789EGN#PBF")
      (footprint "28-Lead Plastic SSOP Linear")
      (description "Buck-Boost Regulator Positive Output Step-Up/Step-Down DC-DC Controller IC, 28-SSOP, -40°C ~ 125°C")
      (fields
        (field (name "MANUFACTURER") "Linear Technology/Analog Devices")
        (field (name "PARTNUM") "LTC3789EGN#PBF-ND")
      )
      (libsource (lib "ea_IC_Power_Reg_Ref_Sw") (part "LTC3789EGN#PBF"))
    )
    (comp (ref "U24")
      (value "DAC80501MDGST")
      (footprint "10-Lead Plastic MSOP Linear")
      (description "10-Bit Digital-to-Analog Converter with Two-Wire Interface")
      (fields
        (field (name "MANUFACTURER") "Texas Instruments")
        (field (name "PARTNUM") "296-DAC80501MDGSTCT-ND")
      )
      (libsource (lib "ea_IC_DAC") (part "DAC80501MDGST"))
    )
    (comp (ref "VD8")
      (value "SMBJ28CA-13-F")
      (footprint "DO-214AA_SMBJ BI")
      (description "TVS 600W, Vbr=31.1V, Vcl=45.4V, Ipp=13.2A,  Bidirectional, SMB, -55°C ~ 150°C")
      (fields
        (field (name "MANUFACTURER") "Diodes Incorporated")
        (field (name "PARTNUM") "SMBJ28CA-FDICT-ND")
      )
      (libsource (lib "ea_TVS_protection") (part "SMBJ28CA-13-F"))
    )
    (comp (ref "VD9")
      (value "SBRT15U50SP5-13")
      (footprint "PowerDI 5")
      (description "Schottky Power Rectifier 15A, 50V, 470mV @ 15A, SMA, -65°C ~ 150°C")
      (fields
        (field (name "MANUFACTURER") "Diodes Incorporated")
        (field (name "PARTNUM") "SBRT15U50SP5-13DICT-ND")
      )
      (libsource (lib "ea_Diodes") (part "SBRT15U50SP5-13"))
    )
    (comp (ref "VD10")
      (value "SMBJ28CA-13-F")
      (footprint "DO-214AA_SMBJ BI")
      (description "TVS 600W, Vbr=31.1V, Vcl=45.4V, Ipp=13.2A,  Bidirectional, SMB, -55°C ~ 150°C")
      (fields
        (field (name "MANUFACTURER") "Diodes Incorporated")
        (field (name "PARTNUM") "SMBJ28CA-FDICT-ND")
      )
      (libsource (lib "ea_TVS_protection") (part "SMBJ28CA-13-F"))
    )
    (comp (ref "VD11")
      (value "Diode")
      (footprint "SOD-323")
      (description "Diode 100V, 250mA (DC), 1.25V @ 150mA, 4ns, SC-76, SOD-323, -65°C ~ 150°C")
      (fields
        (field (name "PARTNAME") "BAS316-TP")
        (field (name "PART NUMBER") "BAS316-TP")
        (field (name "MANUFACTURER") "Micro Commercial Co")
      )
      (libsource (lib "ea_ActiveComps") (part "Diode"))
    )
    (comp (ref "VD13")
      (value "Diode")
      (footprint "SOD-323")
      (description "Diode 100V, 250mA (DC), 1.25V @ 150mA, 4ns, SC-76, SOD-323, -65°C ~ 150°C")
      (fields
        (field (name "PARTNAME") "BAS316-TP")
        (field (name "PART NUMBER") "BAS316-TP")
        (field (name "MANUFACTURER") "Micro Commercial Co")
      )
      (libsource (lib "ea_ActiveComps") (part "Diode"))
    )
    (comp (ref "VD14")
      (value "Diode")
      (footprint "SOD-323")
      (description "Diode 100V, 250mA (DC), 1.25V @ 150mA, 4ns, SC-76, SOD-323, -65°C ~ 150°C")
      (fields
        (field (name "PARTNAME") "BAS316-TP")
        (field (name "PART NUMBER") "BAS316-TP")
        (field (name "MANUFACTURER") "Micro Commercial Co")
      )
      (libsource (lib "ea_ActiveComps") (part "Diode"))
    )
    (comp (ref "X13")
      (value "MKDS5/2-6.35")
      (footprint "MKDS5/2-6.35")
      (description "TERMINAL BLOCK, 2WAY, 6.35 mm, 32A, 500V")
      (fields (field (name "MANUFACTURER") "Phoenix Contacts") (field (name "PARTNUM") "3704683"))
      (libsource (lib "ea_PhoenixContacts") (part "MKDS5/2-6.35"))
    )
    (comp (ref "X14")
      (value "MKDS5/2-6.35")
      (footprint "MKDS5/2-6.35")
      (description "TERMINAL BLOCK, 2WAY, 6.35 mm, 32A, 500V")
      (fields (field (name "MANUFACTURER") "Phoenix Contacts") (field (name "PARTNUM") "3704683"))
      (libsource (lib "ea_PhoenixContacts") (part "MKDS5/2-6.35"))
    )
  )
  (nets
    (net (code "1") (name "+3.3ADCV") (class "Default")
      (node (ref "C51") (pin "1") (pinfunction "1_1") (pintype "passive"))
      (node (ref "C52") (pin "1") (pinfunction "1_1") (pintype "passive"))
      (node (ref "U18") (pin "5") (pinfunction "VS_5") (pintype "passive"))
      (node (ref "U19") (pin "5") (pinfunction "VS_5") (pintype "passive"))
    )
    (net (code "2") (name "+3V3") (class "Default")
      (node (ref "L6") (pin "2") (pinfunction "2_2") (pintype "passive"))
      (node (ref "R68") (pin "2") (pinfunction "2_2") (pintype "passive"))
      (node (ref "R72") (pin "2") (pinfunction "2_2") (pintype "passive"))
      (node (ref "R97") (pin "1") (pinfunction "1_1") (pintype "passive"))
      (node (ref "R98") (pin "1") (pinfunction "1_1") (pintype "passive"))
      (node (ref "R99") (pin "1") (pinfunction "1_1") (pintype "passive"))
    )
    (net (code "3") (name "/ACCID_I+") (class "Default")
      (node (ref "R56") (pin "3") (pinfunction "1_3") (pintype "passive"))
      (node (ref "U19") (pin "2") (pinfunction "IN+_2") (pintype "passive"))
    )
    (net (code "4") (name "/ACCID_I-") (class "Default")
      (node (ref "R56") (pin "4") (pinfunction "1_4") (pintype "passive"))
      (node (ref "U19") (pin "3") (pinfunction "IN-_3") (pintype "passive"))
    )
    (net (code "5") (name "/ACCUM_I+") (class "Default")
      (node (ref "R113") (pin "2") (pinfunction "2_2") (pintype "passive"))
    )
    (net (code "6") (name "/ACCUM_I-") (class "Default")
      (node (ref "R114") (pin "2") (pinfunction "2_2") (pintype "passive"))
    )
    (net (code "7") (name "/ACCUM_ID_I") (class "Default")
      (node (ref "C94") (pin "2") (pinfunction "2_2") (pintype "passive"))
      (node (ref "R105") (pin "2") (pinfunction "2_2") (pintype "passive"))
    )
    (net (code "8") (name "/AIDS_FAULT") (class "Default")
      (node (ref "R72") (pin "1") (pinfunction "1_1") (pintype "passive"))
      (node (ref "U21") (pin "13") (pinfunction "~{FLT}_13") (pintype "passive"))
    )
    (net (code "9") (name "/AIDS_FBC") (class "Default")
      (node (ref "Q9") (pin "1") (pinfunction "G_1") (pintype "passive"))
    )
    (net (code "10") (name "/AIDS_SHDN") (class "Default")
      (node (ref "R78") (pin "2") (pinfunction "2_2") (pintype "passive"))
      (node (ref "U21") (pin "9") (pinfunction "~{SHDN}_9") (pintype "passive"))
    )
    (net (code "11") (name "/BG1") (class "Default")
      (node (ref "Q17") (pin "1") (pinfunction "G_1") (pintype "passive"))
      (node (ref "U23") (pin "23") (pinfunction "BG1_23") (pintype "passive"))
    )
    (net (code "12") (name "/BG2") (class "Default")
      (node (ref "Q18") (pin "1") (pinfunction "G_1") (pintype "passive"))
      (node (ref "U23") (pin "19") (pinfunction "BG2_19") (pintype "passive"))
    )
    (net (code "13") (name "/DCDC_MODE") (class "Default")
      (node (ref "R115") (pin "2") (pinfunction "2_2") (pintype "passive"))
    )
    (net (code "14") (name "/DCDC_PGOOD") (class "Default")
      (node (ref "R95") (pin "1") (pinfunction "1_1") (pintype "passive"))
    )
    (net (code "15") (name "/EN_CHARGER") (class "Default")
      (node (ref "R101") (pin "2") (pinfunction "2_2") (pintype "passive"))
    )
    (net (code "16") (name "/I2C1_SCL") (class "Default")
      (node (ref "R98") (pin "2") (pinfunction "2_2") (pintype "passive"))
      (node (ref "U24") (pin "6") (pinfunction "SCL_6") (pintype "passive"))
    )
    (net (code "17") (name "/I2C1_SDA") (class "Default")
      (node (ref "R97") (pin "2") (pinfunction "2_2") (pintype "passive"))
      (node (ref "U24") (pin "8") (pinfunction "SDA_8") (pintype "passive"))
    )
    (net (code "18") (name "/INTVCC") (class "Default")
      (node (ref "C84") (pin "1") (pinfunction "1_1") (pintype "passive"))
      (node (ref "U23") (pin "21") (pinfunction "INTVCC_21") (pintype "passive"))
      (node (ref "VD13") (pin "2") (pinfunction "A_2") (pintype "passive"))
      (node (ref "VD14") (pin "2") (pinfunction "A_2") (pintype "passive"))
    )
    (net (code "19") (name "/PIDS_FAULT") (class "Default")
      (node (ref "R68") (pin "1") (pinfunction "1_1") (pintype "passive"))
      (node (ref "U20") (pin "13") (pinfunction "~{FLT}_13") (pintype "passive"))
    )
    (net (code "20") (name "/PIDS_SHDN") (class "Default")
      (node (ref "Q10") (pin "1") (pinfunction "G_1") (pintype "passive"))
      (node (ref "R76") (pin "2") (pinfunction "2_2") (pintype "passive"))
    )
    (net (code "21") (name "/PSRC") (class "Default")
      (node (ref "C53") (pin "1") (pinfunction "1_1") (pintype "passive"))
      (node (ref "C54") (pin "1") (pinfunction "1_1") (pintype "passive"))
      (node (ref "Q7") (pin "3") (pinfunction "D_3") (pintype "passive"))
      (node (ref "R61") (pin "2") (pinfunction "2_2") (pintype "passive"))
      (node (ref "R69") (pin "2") (pinfunction "2_2") (pintype "passive"))
      (node (ref "R70") (pin "2") (pinfunction "2_2") (pintype "passive"))
      (node (ref "R75") (pin "1") (pinfunction "1_1") (pintype "passive"))
      (node (ref "U20") (pin "8") (pinfunction "VCC_8") (pintype "passive"))
      (node (ref "VD8") (pin "2") (pinfunction "A_2") (pintype "passive"))
      (node (ref "X14") (pin "1") (pinfunction "1_1") (pintype "passive"))
    )
    (net (code "22") (name "/PSRC_I") (class "Default")
      (node (ref "C92") (pin "2") (pinfunction "2_2") (pintype "passive"))
      (node (ref "R104") (pin "2") (pinfunction "2_2") (pintype "passive"))
    )
    (net (code "23") (name "/PSRC_I+") (class "Default")
      (node (ref "R55") (pin "4") (pinfunction "1_4") (pintype "passive"))
      (node (ref "U18") (pin "2") (pinfunction "IN+_2") (pintype "passive"))
    )
    (net (code "24") (name "/PSRC_I-") (class "Default")
      (node (ref "R55") (pin "3") (pinfunction "1_3") (pintype "passive"))
      (node (ref "U18") (pin "3") (pinfunction "IN-_3") (pintype "passive"))
    )
    (net (code "25") (name "/PSRC_V") (class "Default")
      (node (ref "C59") (pin "2") (pinfunction "2_2") (pintype "passive"))
      (node (ref "R61") (pin "1") (pinfunction "1_1") (pintype "passive"))
      (node (ref "R67") (pin "2") (pinfunction "2_2") (pintype "passive"))
    )
    (net (code "26") (name "/PW2") (class "Default")
      (node (ref "Q7") (pin "2") (pinfunction "S_2") (pintype "passive"))
      (node (ref "Q8") (pin "2") (pinfunction "S_2") (pintype "passive"))
      (node (ref "U20") (pin "5") (pinfunction "SOURCE_5") (pintype "passive"))
    )
    (net (code "27") (name "/PW4") (class "Default")
      (node (ref "C55") (pin "2") (pinfunction "2_2") (pintype "passive"))
      (node (ref "R64") (pin "1") (pinfunction "1_1") (pintype "passive"))
      (node (ref "U20") (pin "6") (pinfunction "HG_6") (pintype "passive"))
    )
    (net (code "28") (name "/PW5") (class "Default")
      (node (ref "Q8") (pin "1") (pinfunction "G_1") (pintype "passive"))
      (node (ref "U20") (pin "4") (pinfunction "DG_4") (pintype "passive"))
    )
    (net (code "29") (name "/PW6") (class "Default")
      (node (ref "Q10") (pin "3") (pinfunction "D_3") (pintype "passive"))
      (node (ref "R75") (pin "2") (pinfunction "2_2") (pintype "passive"))
      (node (ref "U20") (pin "9") (pinfunction "~{SHDN}_9") (pintype "passive"))
    )
    (net (code "30") (name "/PW9") (class "Default")
      (node (ref "Q7") (pin "1") (pinfunction "G_1") (pintype "passive"))
      (node (ref "R64") (pin "2") (pinfunction "2_2") (pintype "passive"))
    )
    (net (code "31") (name "/PWR24_V") (class "Default")
      (node (ref "C74") (pin "2") (pinfunction "2_2") (pintype "passive"))
      (node (ref "R81") (pin "1") (pinfunction "1_1") (pintype "passive"))
      (node (ref "R83") (pin "2") (pinfunction "2_2") (pintype "passive"))
    )
    (net (code "32") (name "/SNS+") (class "Default")
      (node (ref "C78") (pin "1") (pinfunction "1_1") (pintype "passive"))
      (node (ref "R85") (pin "2") (pinfunction "2_2") (pintype "passive"))
      (node (ref "U23") (pin "3") (pinfunction "SENSE+_3") (pintype "passive"))
    )
    (net (code "33") (name "/SNS-") (class "Default")
      (node (ref "C78") (pin "2") (pinfunction "2_2") (pintype "passive"))
      (node (ref "R87") (pin "2") (pinfunction "2_2") (pintype "passive"))
      (node (ref "U23") (pin "4") (pinfunction "SENSE-_4") (pintype "passive"))
    )
    (net (code "34") (name "/SW1") (class "Default")
      (node (ref "C83") (pin "2") (pinfunction "2_2") (pintype "passive"))
      (node (ref "L5") (pin "1") (pinfunction "1_1") (pintype "passive"))
      (node (ref "Q12") (pin "2") (pinfunction "S_2") (pintype "passive"))
      (node (ref "Q13") (pin "2") (pinfunction "S_2") (pintype "passive"))
      (node (ref "Q17") (pin "3") (pinfunction "D_3") (pintype "passive"))
      (node (ref "U23") (pin "27") (pinfunction "SW1_27") (pintype "passive"))
    )
    (net (code "35") (name "/SW2") (class "Default")
      (node (ref "C85") (pin "2") (pinfunction "2_2") (pintype "passive"))
      (node (ref "L5") (pin "2") (pinfunction "2_2") (pintype "passive"))
      (node (ref "Q14") (pin "2") (pinfunction "S_2") (pintype "passive"))
      (node (ref "Q18") (pin "3") (pinfunction "D_3") (pintype "passive"))
      (node (ref "U23") (pin "16") (pinfunction "SW2_16") (pintype "passive"))
      (node (ref "VD9") (pin "1") (pinfunction "1_1") (pintype "passive"))
      (node (ref "VD9") (pin "2") (pinfunction "2_2") (pintype "passive"))
    )
    (net (code "36") (name "/TG1") (class "Default")
      (node (ref "Q12") (pin "1") (pinfunction "G_1") (pintype "passive"))
      (node (ref "Q13") (pin "1") (pinfunction "G_1") (pintype "passive"))
      (node (ref "U23") (pin "26") (pinfunction "TG1_26") (pintype "passive"))
    )
    (net (code "37") (name "/TG2") (class "Default")
      (node (ref "Q14") (pin "1") (pinfunction "G_1") (pintype "passive"))
      (node (ref "U23") (pin "17") (pinfunction "TG2_17") (pintype "passive"))
    )
    (net (code "38") (name "/VFB") (class "Default")
      (node (ref "R100") (pin "2") (pinfunction "2_2") (pintype "passive"))
      (node (ref "R94") (pin "1") (pinfunction "1_1") (pintype "passive"))
      (node (ref "R96") (pin "1") (pinfunction "1_1") (pintype "passive"))
      (node (ref "U23") (pin "1") (pinfunction "FB_1") (pintype "passive"))
    )
    (net (code "39") (name "/VIN") (class "Default")
      (node (ref "C75") (pin "1") (pinfunction "1_1") (pintype "passive"))
      (node (ref "C76") (pin "1") (pinfunction "1_1") (pintype "passive"))
      (node (ref "R84") (pin "1") (pinfunction "1_1") (pintype "passive"))
      (node (ref "U23") (pin "22") (pinfunction "VIN_22") (pintype "passive"))
    )
    (net (code "40") (name "/VINSNS") (class "Default")
      (node (ref "C87") (pin "1") (pinfunction "1_1") (pintype "passive"))
      (node (ref "R82") (pin "1") (pinfunction "1_1") (pintype "passive"))
      (node (ref "U23") (pin "10") (pinfunction "VINSNS_10") (pintype "passive"))
    )
    (net (code "41") (name "/VOUTSNS") (class "Default")
      (node (ref "C88") (pin "1") (pinfunction "1_1") (pintype "passive"))
      (node (ref "R102") (pin "1") (pinfunction "1_1") (pintype "passive"))
      (node (ref "U23") (pin "11") (pinfunction "VOUTSNS_11") (pintype "passive"))
    )
    (net (code "42") (name "ACC_DC_BUS") (class "Default")
      (node (ref "C61") (pin "1") (pinfunction "1_1") (pintype "passive"))
      (node (ref "C62") (pin "1") (pinfunction "1_1") (pintype "passive"))
      (node (ref "C63") (pin "1") (pinfunction "1_1") (pintype "passive"))
      (node (ref "C64") (pin "1") (pinfunction "1_1") (pintype "passive"))
      (node (ref "C65") (pin "1") (pinfunction "1_1") (pintype "passive"))
      (node (ref "C66") (pin "1") (pinfunction "1_1") (pintype "passive"))
      (node (ref "Q14") (pin "3") (pinfunction "D_3") (pintype "passive"))
      (node (ref "Q6") (pin "3") (pinfunction "D_3") (pintype "passive"))
      (node (ref "R102") (pin "2") (pinfunction "2_2") (pintype "passive"))
      (node (ref "R71") (pin "2") (pinfunction "2_2") (pintype "passive"))
      (node (ref "R96") (pin "2") (pinfunction "2_2") (pintype "passive"))
      (node (ref "VD9") (pin "3") (pinfunction "3_3") (pintype "passive"))
    )
    (net (code "43") (name "AGND") (class "Default")
      (node (ref "C51") (pin "2") (pinfunction "2_2") (pintype "passive"))
      (node (ref "C52") (pin "2") (pinfunction "2_2") (pintype "passive"))
      (node (ref "C59") (pin "1") (pinfunction "1_1") (pintype "passive"))
      (node (ref "C74") (pin "1") (pinfunction "1_1") (pintype "passive"))
      (node (ref "C92") (pin "1") (pinfunction "1_1") (pintype "passive"))
      (node (ref "C94") (pin "1") (pinfunction "1_1") (pintype "passive"))
      (node (ref "R67") (pin "1") (pinfunction "1_1") (pintype "passive"))
      (node (ref "R83") (pin "1") (pinfunction "1_1") (pintype "passive"))
      (node (ref "U18") (pin "4") (pinfunction "GND_4") (pintype "passive"))
      (node (ref "U19") (pin "4") (pinfunction "GND_4") (pintype "passive"))
    )
    (net (code "44") (name "CGND") (class "Default")
      (node (ref "B3") (pin "2") (pinfunction "2_2") (pintype "passive"))
      (node (ref "C79") (pin "1") (pinfunction "1_1") (pintype "passive"))
      (node (ref "C80") (pin "1") (pinfunction "1_1") (pintype "passive"))
      (node (ref "C81") (pin "1") (pinfunction "1_1") (pintype "passive"))
      (node (ref "C82") (pin "1") (pinfunction "1_1") (pintype "passive"))
      (node (ref "C86") (pin "2") (pinfunction "2_2") (pintype "passive"))
      (node (ref "C87") (pin "2") (pinfunction "2_2") (pintype "passive"))
      (node (ref "C88") (pin "2") (pinfunction "2_2") (pintype "passive"))
      (node (ref "R100") (pin "1") (pinfunction "1_1") (pintype "passive"))
      (node (ref "R90") (pin "1") (pinfunction "1_1") (pintype "passive"))
      (node (ref "U23") (pin "12") (pinfunction "ILIM_12") (pintype "passive"))
      (node (ref "U23") (pin "6") (pinfunction "SGND_6") (pintype "passive"))
      (node (ref "U24") (pin "4") (pinfunction "AGND_4") (pintype "passive"))
      (node (ref "U24") (pin "7") (pinfunction "A0_7") (pintype "passive"))
    )
    (net (code "45") (name "GND") (class "Default")
      (node (ref "B7") (pin "1") (pinfunction "1_1") (pintype "passive"))
    )
    (net (code "46") (name "Net-(C80-Pad2)") (class "Default")
      (node (ref "C80") (pin "2") (pinfunction "2_2") (pintype "passive"))
      (node (ref "R93") (pin "2") (pinfunction "2_2") (pintype "passive"))
    )
    (net (code "47") (name "Net-(Q5-D)") (class "Default")
      (node (ref "Q5") (pin "3") (pinfunction "D_3") (pintype "passive"))
      (node (ref "R56") (pin "1") (pinfunction "1_1") (pintype "passive"))
      (node (ref "U21") (pin "2") (pinfunction "SENSE_2") (pintype "passive"))
    )
    (net (code "48") (name "Net-(Q5-G)") (class "Default")
      (node (ref "Q5") (pin "1") (pinfunction "G_1") (pintype "passive"))
      (node (ref "U21") (pin "4") (pinfunction "DG_4") (pintype "passive"))
    )
    (net (code "49") (name "Net-(Q5-S)") (class "Default")
      (node (ref "Q5") (pin "2") (pinfunction "S_2") (pintype "passive"))
      (node (ref "Q6") (pin "2") (pinfunction "S_2") (pintype "passive"))
      (node (ref "U21") (pin "5") (pinfunction "SOURCE_5") (pintype "passive"))
    )
    (net (code "50") (name "Net-(Q6-G)") (class "Default")
      (node (ref "Q6") (pin "1") (pinfunction "G_1") (pintype "passive"))
      (node (ref "R66") (pin "2") (pinfunction "2_2") (pintype "passive"))
    )
    (net (code "51") (name "Net-(Q8-D)") (class "Default")
      (node (ref "Q8") (pin "3") (pinfunction "D_3") (pintype "passive"))
      (node (ref "R55") (pin "2") (pinfunction "2_2") (pintype "passive"))
      (node (ref "U20") (pin "2") (pinfunction "SENSE_2") (pintype "passive"))
    )
    (net (code "52") (name "Net-(Q9-D)") (class "Default")
      (node (ref "C57") (pin "2") (pinfunction "2_2") (pintype "passive"))
      (node (ref "Q9") (pin "3") (pinfunction "D_3") (pintype "passive"))
      (node (ref "R60") (pin "2") (pinfunction "2_2") (pintype "passive"))
    )
    (net (code "53") (name "Net-(Q17-S)") (class "Default")
      (node (ref "Q17") (pin "2") (pinfunction "S_2") (pintype "passive"))
      (node (ref "Q18") (pin "2") (pinfunction "S_2") (pintype "passive"))
      (node (ref "R86") (pin "2") (pinfunction "2_2") (pintype "passive"))
    )
    (net (code "54") (name "Net-(R85-Pad1)") (class "Default")
      (node (ref "R85") (pin "1") (pinfunction "1_1") (pintype "passive"))
      (node (ref "R86") (pin "4") (pinfunction "1_4") (pintype "passive"))
    )
    (net (code "55") (name "Net-(R86-1-Pad3)") (class "Default")
      (node (ref "R86") (pin "3") (pinfunction "1_3") (pintype "passive"))
      (node (ref "R87") (pin "1") (pinfunction "1_1") (pintype "passive"))
    )
    (net (code "56") (name "Net-(U18-OUT)") (class "Default")
      (node (ref "R104") (pin "1") (pinfunction "1_1") (pintype "passive"))
      (node (ref "U18") (pin "8") (pinfunction "OUT_8") (pintype "passive"))
    )
    (net (code "57") (name "Net-(U19-OUT)") (class "Default")
      (node (ref "R105") (pin "1") (pinfunction "1_1") (pintype "passive"))
      (node (ref "U19") (pin "8") (pinfunction "OUT_8") (pintype "passive"))
    )
    (net (code "58") (name "Net-(U20-FB)") (class "Default")
      (node (ref "R57") (pin "1") (pinfunction "1_1") (pintype "passive"))
      (node (ref "R62") (pin "1") (pinfunction "1_1") (pintype "passive"))
      (node (ref "U20") (pin "16") (pinfunction "FB_16") (pintype "passive"))
    )
    (net (code "59") (name "Net-(U20-OV)") (class "Default")
      (node (ref "R70") (pin "1") (pinfunction "1_1") (pintype "passive"))
      (node (ref "R74") (pin "2") (pinfunction "2_2") (pintype "passive"))
      (node (ref "U20") (pin "11") (pinfunction "OV_11") (pintype "passive"))
    )
    (net (code "60") (name "Net-(U20-TMR)") (class "Default")
      (node (ref "C60") (pin "2") (pinfunction "2_2") (pintype "passive"))
      (node (ref "U20") (pin "15") (pinfunction "TMR_15") (pintype "passive"))
    )
    (net (code "61") (name "Net-(U20-UV)") (class "Default")
      (node (ref "R69") (pin "1") (pinfunction "1_1") (pintype "passive"))
      (node (ref "R73") (pin "2") (pinfunction "2_2") (pintype "passive"))
      (node (ref "U20") (pin "10") (pinfunction "UV_10") (pintype "passive"))
    )
    (net (code "62") (name "Net-(U21-FB)") (class "Default")
      (node (ref "R59") (pin "1") (pinfunction "1_1") (pintype "passive"))
      (node (ref "R60") (pin "1") (pinfunction "1_1") (pintype "passive"))
      (node (ref "R65") (pin "2") (pinfunction "2_2") (pintype "passive"))
      (node (ref "U21") (pin "16") (pinfunction "FB_16") (pintype "passive"))
    )
    (net (code "63") (name "Net-(U21-HG)") (class "Default")
      (node (ref "C56") (pin "2") (pinfunction "2_2") (pintype "passive"))
      (node (ref "R66") (pin "1") (pinfunction "1_1") (pintype "passive"))
      (node (ref "U21") (pin "6") (pinfunction "HG_6") (pintype "passive"))
    )
    (net (code "64") (name "Net-(U21-OV)") (class "Default")
      (node (ref "R77") (pin "1") (pinfunction "1_1") (pintype "passive"))
      (node (ref "U21") (pin "11") (pinfunction "OV_11") (pintype "passive"))
    )
    (net (code "65") (name "Net-(U21-UV)") (class "Default")
      (node (ref "R71") (pin "1") (pinfunction "1_1") (pintype "passive"))
      (node (ref "U21") (pin "10") (pinfunction "UV_10") (pintype "passive"))
      (node (ref "U21") (pin "8") (pinfunction "VCC_8") (pintype "passive"))
    )
    (net (code "66") (name "Net-(U23-BOOST1)") (class "Default")
      (node (ref "C83") (pin "1") (pinfunction "1_1") (pintype "passive"))
      (node (ref "U23") (pin "25") (pinfunction "BOOST1_25") (pintype "passive"))
      (node (ref "VD13") (pin "1") (pinfunction "C_1") (pintype "passive"))
    )
    (net (code "67") (name "Net-(U23-BOOST2)") (class "Default")
      (node (ref "C85") (pin "1") (pinfunction "1_1") (pintype "passive"))
      (node (ref "U23") (pin "18") (pinfunction "BOOST2_18") (pintype "passive"))
      (node (ref "VD14") (pin "1") (pinfunction "C_1") (pintype "passive"))
    )
    (net (code "68") (name "Net-(U23-FREQ)") (class "Default")
      (node (ref "R90") (pin "2") (pinfunction "2_2") (pintype "passive"))
      (node (ref "U23") (pin "8") (pinfunction "FREQ_8") (pintype "passive"))
    )
    (net (code "69") (name "Net-(U23-IOSENSE+)") (class "Default")
      (node (ref "C104") (pin "2") (pinfunction "2_2") (pintype "passive"))
      (node (ref "R114") (pin "1") (pinfunction "1_1") (pintype "passive"))
      (node (ref "U23") (pin "13") (pinfunction "IOSENSE+_13") (pintype "passive"))
    )
    (net (code "70") (name "Net-(U23-IOSENSE-)") (class "Default")
      (node (ref "C104") (pin "1") (pinfunction "1_1") (pintype "passive"))
      (node (ref "R113") (pin "1") (pinfunction "1_1") (pintype "passive"))
      (node (ref "U23") (pin "14") (pinfunction "IOSENSE-_14") (pintype "passive"))
    )
    (net (code "71") (name "Net-(U23-ITH)") (class "Default")
      (node (ref "C79") (pin "2") (pinfunction "2_2") (pintype "passive"))
      (node (ref "R93") (pin "1") (pinfunction "1_1") (pintype "passive"))
      (node (ref "U23") (pin "5") (pinfunction "ITH_5") (pintype "passive"))
    )
    (net (code "72") (name "Net-(U23-MODE)") (class "Default")
      (node (ref "R115") (pin "1") (pinfunction "1_1") (pintype "passive"))
      (node (ref "U23") (pin "7") (pinfunction "MODE_7") (pintype "passive"))
    )
    (net (code "73") (name "Net-(U23-PGOOD)") (class "Default")
      (node (ref "R95") (pin "2") (pinfunction "2_2") (pintype "passive"))
      (node (ref "R99") (pin "2") (pinfunction "2_2") (pintype "passive"))
      (node (ref "U23") (pin "28") (pinfunction "PGOOD_28") (pintype "passive"))
    )
    (net (code "74") (name "Net-(U23-RUN)") (class "Default")
      (node (ref "R101") (pin "1") (pinfunction "1_1") (pintype "passive"))
      (node (ref "R89") (pin "2") (pinfunction "2_2") (pintype "passive"))
      (node (ref "U23") (pin "9") (pinfunction "RUN_9") (pintype "passive"))
    )
    (net (code "75") (name "Net-(U23-SS)") (class "Default")
      (node (ref "C81") (pin "2") (pinfunction "2_2") (pintype "passive"))
      (node (ref "U23") (pin "2") (pinfunction "SS_2") (pintype "passive"))
    )
    (net (code "76") (name "Net-(U24-SPI2C)") (class "Default")
      (node (ref "C86") (pin "1") (pinfunction "1_1") (pintype "passive"))
      (node (ref "L6") (pin "1") (pinfunction "1_1") (pintype "passive"))
      (node (ref "U24") (pin "1") (pinfunction "VDD_1") (pintype "passive"))
      (node (ref "U24") (pin "5") (pinfunction "SPI2C_5") (pintype "passive"))
    )
    (net (code "77") (name "Net-(U24-VOUT)") (class "Default")
      (node (ref "R94") (pin "2") (pinfunction "2_2") (pintype "passive"))
      (node (ref "U24") (pin "2") (pinfunction "VOUT_2") (pintype "passive"))
    )
    (net (code "78") (name "Net-(U24-VREF)") (class "Default")
      (node (ref "C82") (pin "2") (pinfunction "2_2") (pintype "passive"))
      (node (ref "U24") (pin "10") (pinfunction "VREF_10") (pintype "passive"))
    )
    (net (code "79") (name "Net-(VD11-C)") (class "Default")
      (node (ref "R84") (pin "2") (pinfunction "2_2") (pintype "passive"))
      (node (ref "VD11") (pin "1") (pinfunction "C_1") (pintype "passive"))
    )
    (net (code "80") (name "PGND") (class "Default")
      (node (ref "B3") (pin "1") (pinfunction "1_1") (pintype "passive"))
      (node (ref "B7") (pin "2") (pinfunction "2_2") (pintype "passive"))
      (node (ref "C53") (pin "2") (pinfunction "2_2") (pintype "passive"))
      (node (ref "C54") (pin "2") (pinfunction "2_2") (pintype "passive"))
      (node (ref "C55") (pin "1") (pinfunction "1_1") (pintype "passive"))
      (node (ref "C56") (pin "1") (pinfunction "1_1") (pintype "passive"))
      (node (ref "C57") (pin "1") (pinfunction "1_1") (pintype "passive"))
      (node (ref "C60") (pin "1") (pinfunction "1_1") (pintype "passive"))
      (node (ref "C61") (pin "2") (pinfunction "2_2") (pintype "passive"))
      (node (ref "C62") (pin "2") (pinfunction "2_2") (pintype "passive"))
      (node (ref "C63") (pin "2") (pinfunction "2_2") (pintype "passive"))
      (node (ref "C64") (pin "2") (pinfunction "2_2") (pintype "passive"))
      (node (ref "C65") (pin "2") (pinfunction "2_2") (pintype "passive"))
      (node (ref "C66") (pin "2") (pinfunction "2_2") (pintype "passive"))
      (node (ref "C67") (pin "2") (pinfunction "2_2") (pintype "passive"))
      (node (ref "C68") (pin "2") (pinfunction "2_2") (pintype "passive"))
      (node (ref "C69") (pin "2") (pinfunction "2_2") (pintype "passive"))
      (node (ref "C70") (pin "2") (pinfunction "2_2") (pintype "passive"))
      (node (ref "C71") (pin "2") (pinfunction "2_2") (pintype "passive"))
      (node (ref "C72") (pin "2") (pinfunction "2_2") (pintype "passive"))
      (node (ref "C73") (pin "2") (pinfunction "2_2") (pintype "passive"))
      (node (ref "C75") (pin "2") (pinfunction "2_2") (pintype "passive"))
      (node (ref "C76") (pin "2") (pinfunction "2_2") (pintype "passive"))
      (node (ref "C84") (pin "2") (pinfunction "2_2") (pintype "passive"))
      (node (ref "Q10") (pin "2") (pinfunction "S_2") (pintype "passive"))
      (node (ref "Q9") (pin "2") (pinfunction "S_2") (pintype "passive"))
      (node (ref "R62") (pin "2") (pinfunction "2_2") (pintype "passive"))
      (node (ref "R65") (pin "1") (pinfunction "1_1") (pintype "passive"))
      (node (ref "R73") (pin "1") (pinfunction "1_1") (pintype "passive"))
      (node (ref "R74") (pin "1") (pinfunction "1_1") (pintype "passive"))
      (node (ref "R76") (pin "1") (pinfunction "1_1") (pintype "passive"))
      (node (ref "R77") (pin "2") (pinfunction "2_2") (pintype "passive"))
      (node (ref "R78") (pin "1") (pinfunction "1_1") (pintype "passive"))
      (node (ref "R86") (pin "1") (pinfunction "1_1") (pintype "passive"))
      (node (ref "R89") (pin "1") (pinfunction "1_1") (pintype "passive"))
      (node (ref "U20") (pin "12") (pinfunction "GND_12") (pintype "passive"))
      (node (ref "U21") (pin "12") (pinfunction "GND_12") (pintype "passive"))
      (node (ref "U21") (pin "15") (pinfunction "TMR_15") (pintype "passive"))
      (node (ref "U23") (pin "15") (pinfunction "TRIM_15") (pintype "passive"))
      (node (ref "U23") (pin "20") (pinfunction "EXTVCC_20") (pintype "passive"))
      (node (ref "U23") (pin "24") (pinfunction "PGND_24") (pintype "passive"))
      (node (ref "VD10") (pin "1") (pinfunction "C_1") (pintype "passive"))
      (node (ref "VD8") (pin "1") (pinfunction "C_1") (pintype "passive"))
      (node (ref "X13") (pin "1") (pinfunction "1_1") (pintype "passive"))
      (node (ref "X14") (pin "2") (pinfunction "2_2") (pintype "passive"))
    )
    (net (code "81") (name "SYS_PWR") (class "Default")
      (node (ref "C67") (pin "1") (pinfunction "1_1") (pintype "passive"))
      (node (ref "C68") (pin "1") (pinfunction "1_1") (pintype "passive"))
      (node (ref "C69") (pin "1") (pinfunction "1_1") (pintype "passive"))
      (node (ref "C70") (pin "1") (pinfunction "1_1") (pintype "passive"))
      (node (ref "C71") (pin "1") (pinfunction "1_1") (pintype "passive"))
      (node (ref "C72") (pin "1") (pinfunction "1_1") (pintype "passive"))
      (node (ref "C73") (pin "1") (pinfunction "1_1") (pintype "passive"))
      (node (ref "Q12") (pin "3") (pinfunction "D_3") (pintype "passive"))
      (node (ref "Q13") (pin "3") (pinfunction "D_3") (pintype "passive"))
      (node (ref "R55") (pin "1") (pinfunction "1_1") (pintype "passive"))
      (node (ref "R56") (pin "2") (pinfunction "2_2") (pintype "passive"))
      (node (ref "R57") (pin "2") (pinfunction "2_2") (pintype "passive"))
      (node (ref "R59") (pin "2") (pinfunction "2_2") (pintype "passive"))
      (node (ref "R81") (pin "2") (pinfunction "2_2") (pintype "passive"))
      (node (ref "R82") (pin "2") (pinfunction "2_2") (pintype "passive"))
      (node (ref "U20") (pin "1") (pinfunction "OUT_1") (pintype "passive"))
      (node (ref "U21") (pin "1") (pinfunction "OUT_1") (pintype "passive"))
      (node (ref "VD10") (pin "2") (pinfunction "A_2") (pintype "passive"))
      (node (ref "VD11") (pin "2") (pinfunction "A_2") (pintype "passive"))
      (node (ref "X13") (pin "2") (pinfunction "2_2") (pintype "passive"))
    )
    (net (code "82") (name "VREF_1.65V") (class "Default")
      (node (ref "U18") (pin "6") (pinfunction "REF2_6") (pintype "passive"))
      (node (ref "U18") (pin "7") (pinfunction "REF1_7") (pintype "passive"))
      (node (ref "U19") (pin "6") (pinfunction "REF2_6") (pintype "passive"))
      (node (ref "U19") (pin "7") (pinfunction "REF1_7") (pintype "passive"))
    )
    (net (code "83") (name "unconnected-(U18-NC-Pad1)") (class "Default")
      (node (ref "U18") (pin "1") (pinfunction "NC_1") (pintype "passive"))
    )
    (net (code "84") (name "unconnected-(U19-NC-Pad1)") (class "Default")
      (node (ref "U19") (pin "1") (pinfunction "NC_1") (pintype "passive"))
    )
    (net (code "85") (name "unconnected-(U20-ENOUT-Pad14)") (class "Default")
      (node (ref "U20") (pin "14") (pinfunction "ENOUT_14") (pintype "passive"))
    )
    (net (code "86") (name "unconnected-(U20-NC-Pad3)") (class "Default")
      (node (ref "U20") (pin "3") (pinfunction "NC_3") (pintype "passive"))
    )
    (net (code "87") (name "unconnected-(U20-NC-Pad7)") (class "Default")
      (node (ref "U20") (pin "7") (pinfunction "NC_7") (pintype "passive"))
    )
    (net (code "88") (name "unconnected-(U21-ENOUT-Pad14)") (class "Default")
      (node (ref "U21") (pin "14") (pinfunction "ENOUT_14") (pintype "passive"))
    )
    (net (code "89") (name "unconnected-(U21-NC-Pad3)") (class "Default")
      (node (ref "U21") (pin "3") (pinfunction "NC_3") (pintype "passive"))
    )
    (net (code "90") (name "unconnected-(U21-NC-Pad7)") (class "Default")
      (node (ref "U21") (pin "7") (pinfunction "NC_7") (pintype "passive"))
    )
    (net (code "91") (name "unconnected-(U24-NC-Pad3)") (class "Default")
      (node (ref "U24") (pin "3") (pinfunction "NC_3") (pintype "passive"))
    )
    (net (code "92") (name "unconnected-(U24-NC-Pad9)") (class "Default")
      (node (ref "U24") (pin "9") (pinfunction "NC_9") (pintype "passive"))
    )
  )
)
